# SFPGA_power.net
KiCad netlist of a schematic drawn in Altium Designer
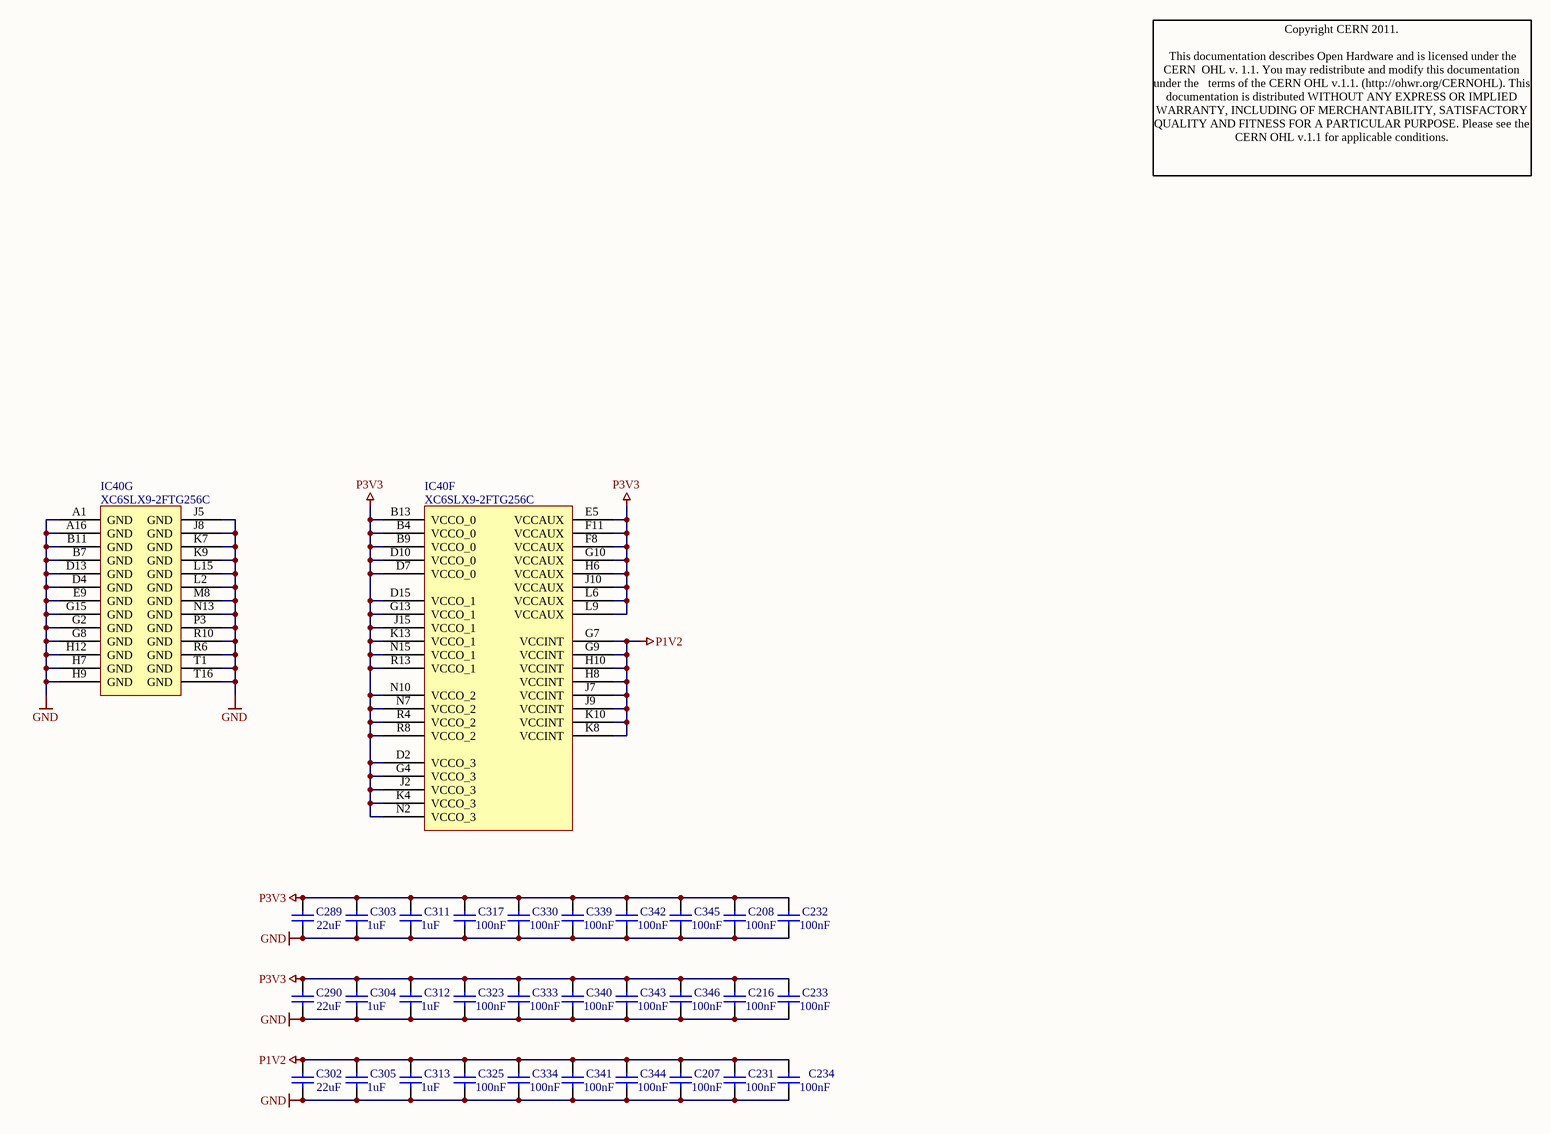
[diagram p0: SFPGA_power.SchDoc]

(export (version "E")
  (design (tool "Eeschema 10.0.6"))
  (components
    (comp (ref "C207")
      (value "100nF")
      (footprint "CAPC1005X55N")
      (description "Non-polarised capacitor")
      (fields
        (field (name "PART NUMBER") "CC0402_100NF_16V_10%_X7R")
        (field (name "VOLTAGE") "16V")
        (field (name "AUTHOR") "CERN DEM JLC")
      )
      (libsource (lib "Capacitors") (part "Capacitor - non polarized"))
    )
    (comp (ref "C208")
      (value "100nF")
      (footprint "CAPC1005X55N")
      (description "Non-polarised capacitor")
      (fields
        (field (name "PART NUMBER") "CC0402_100NF_16V_10%_X7R")
        (field (name "VOLTAGE") "16V")
        (field (name "AUTHOR") "CERN DEM JLC")
      )
      (libsource (lib "Capacitors") (part "Capacitor - non polarized"))
    )
    (comp (ref "C216")
      (value "100nF")
      (footprint "CAPC1005X55N")
      (description "Non-polarised capacitor")
      (fields
        (field (name "PART NUMBER") "CC0402_100NF_16V_10%_X7R")
        (field (name "VOLTAGE") "16V")
        (field (name "AUTHOR") "CERN DEM JLC")
      )
      (libsource (lib "Capacitors") (part "Capacitor - non polarized"))
    )
    (comp (ref "C231")
      (value "100nF")
      (footprint "CAPC1005X55N")
      (description "Non-polarised capacitor")
      (fields
        (field (name "PART NUMBER") "CC0402_100NF_16V_10%_X7R")
        (field (name "VOLTAGE") "16V")
        (field (name "AUTHOR") "CERN DEM JLC")
      )
      (libsource (lib "Capacitors") (part "Capacitor - non polarized"))
    )
    (comp (ref "C232")
      (value "100nF")
      (footprint "CAPC1005X55N")
      (description "Non-polarised capacitor")
      (fields
        (field (name "PART NUMBER") "CC0402_100NF_16V_10%_X7R")
        (field (name "VOLTAGE") "16V")
        (field (name "AUTHOR") "CERN DEM JLC")
      )
      (libsource (lib "Capacitors") (part "Capacitor - non polarized"))
    )
    (comp (ref "C233")
      (value "100nF")
      (footprint "CAPC1005X55N")
      (description "Non-polarised capacitor")
      (fields
        (field (name "PART NUMBER") "CC0402_100NF_16V_10%_X7R")
        (field (name "VOLTAGE") "16V")
        (field (name "AUTHOR") "CERN DEM JLC")
      )
      (libsource (lib "Capacitors") (part "Capacitor - non polarized"))
    )
    (comp (ref "C234")
      (value "100nF")
      (footprint "CAPC1005X55N")
      (description "Non-polarised capacitor")
      (fields
        (field (name "PART NUMBER") "CC0402_100NF_16V_10%_X7R")
        (field (name "VOLTAGE") "16V")
        (field (name "AUTHOR") "CERN DEM JLC")
      )
      (libsource (lib "Capacitors") (part "Capacitor - non polarized"))
    )
    (comp (ref "C289")
      (value "22uF")
      (footprint "CAPC3216X180N")
      (description "Non-polarised capacitor")
      (fields
        (field (name "PART NUMBER") "CC1206_22UF_10V_10%_X7R")
        (field (name "VOLTAGE") "10V")
        (field (name "AUTHOR") "CERN DEM JLC")
      )
      (libsource (lib "Capacitors") (part "Capacitor - non polarized"))
    )
    (comp (ref "C290")
      (value "22uF")
      (footprint "CAPC3216X180N")
      (description "Non-polarised capacitor")
      (fields
        (field (name "PART NUMBER") "CC1206_22UF_10V_10%_X7R")
        (field (name "VOLTAGE") "10V")
        (field (name "AUTHOR") "CERN DEM JLC")
      )
      (libsource (lib "Capacitors") (part "Capacitor - non polarized"))
    )
    (comp (ref "C302")
      (value "22uF")
      (footprint "CAPC3216X180N")
      (description "Non-polarised capacitor")
      (fields
        (field (name "PART NUMBER") "CC1206_22UF_10V_10%_X7R")
        (field (name "VOLTAGE") "10V")
        (field (name "AUTHOR") "CERN DEM JLC")
      )
      (libsource (lib "Capacitors") (part "Capacitor - non polarized"))
    )
    (comp (ref "C303")
      (value "1uF")
      (footprint "CAPC1608X87N")
      (description "Non-polarised capacitor")
      (fields
        (field (name "PART NUMBER") "CC0603_1UF_16V_10%_X7R")
        (field (name "VOLTAGE") "16V")
        (field (name "AUTHOR") "CERN DEM JLC")
      )
      (libsource (lib "Capacitors") (part "Capacitor - non polarized"))
    )
    (comp (ref "C304")
      (value "1uF")
      (footprint "CAPC1608X87N")
      (description "Non-polarised capacitor")
      (fields
        (field (name "PART NUMBER") "CC0603_1UF_16V_10%_X7R")
        (field (name "VOLTAGE") "16V")
        (field (name "AUTHOR") "CERN DEM JLC")
      )
      (libsource (lib "Capacitors") (part "Capacitor - non polarized"))
    )
    (comp (ref "C305")
      (value "1uF")
      (footprint "CAPC1608X87N")
      (description "Non-polarised capacitor")
      (fields
        (field (name "PART NUMBER") "CC0603_1UF_16V_10%_X7R")
        (field (name "VOLTAGE") "16V")
        (field (name "AUTHOR") "CERN DEM JLC")
      )
      (libsource (lib "Capacitors") (part "Capacitor - non polarized"))
    )
    (comp (ref "C311")
      (value "1uF")
      (footprint "CAPC1608X87N")
      (description "Non-polarised capacitor")
      (fields
        (field (name "PART NUMBER") "CC0603_1UF_16V_10%_X7R")
        (field (name "VOLTAGE") "16V")
        (field (name "AUTHOR") "CERN DEM JLC")
      )
      (libsource (lib "Capacitors") (part "Capacitor - non polarized"))
    )
    (comp (ref "C312")
      (value "1uF")
      (footprint "CAPC1608X87N")
      (description "Non-polarised capacitor")
      (fields
        (field (name "PART NUMBER") "CC0603_1UF_16V_10%_X7R")
        (field (name "VOLTAGE") "16V")
        (field (name "AUTHOR") "CERN DEM JLC")
      )
      (libsource (lib "Capacitors") (part "Capacitor - non polarized"))
    )
    (comp (ref "C313")
      (value "1uF")
      (footprint "CAPC1608X87N")
      (description "Non-polarised capacitor")
      (fields
        (field (name "PART NUMBER") "CC0603_1UF_16V_10%_X7R")
        (field (name "VOLTAGE") "16V")
        (field (name "AUTHOR") "CERN DEM JLC")
      )
      (libsource (lib "Capacitors") (part "Capacitor - non polarized"))
    )
    (comp (ref "C317")
      (value "100nF")
      (footprint "CAPC1005X55N")
      (description "Non-polarised capacitor")
      (fields
        (field (name "PART NUMBER") "CC0402_100NF_16V_10%_X7R")
        (field (name "VOLTAGE") "16V")
        (field (name "AUTHOR") "CERN DEM JLC")
      )
      (libsource (lib "Capacitors") (part "Capacitor - non polarized"))
    )
    (comp (ref "C323")
      (value "100nF")
      (footprint "CAPC1005X55N")
      (description "Non-polarised capacitor")
      (fields
        (field (name "PART NUMBER") "CC0402_100NF_16V_10%_X7R")
        (field (name "VOLTAGE") "16V")
        (field (name "AUTHOR") "CERN DEM JLC")
      )
      (libsource (lib "Capacitors") (part "Capacitor - non polarized"))
    )
    (comp (ref "C325")
      (value "100nF")
      (footprint "CAPC1005X55N")
      (description "Non-polarised capacitor")
      (fields
        (field (name "PART NUMBER") "CC0402_100NF_16V_10%_X7R")
        (field (name "VOLTAGE") "16V")
        (field (name "AUTHOR") "CERN DEM JLC")
      )
      (libsource (lib "Capacitors") (part "Capacitor - non polarized"))
    )
    (comp (ref "C330")
      (value "100nF")
      (footprint "CAPC1005X55N")
      (description "Non-polarised capacitor")
      (fields
        (field (name "PART NUMBER") "CC0402_100NF_16V_10%_X7R")
        (field (name "VOLTAGE") "16V")
        (field (name "AUTHOR") "CERN DEM JLC")
      )
      (libsource (lib "Capacitors") (part "Capacitor - non polarized"))
    )
    (comp (ref "C333")
      (value "100nF")
      (footprint "CAPC1005X55N")
      (description "Non-polarised capacitor")
      (fields
        (field (name "PART NUMBER") "CC0402_100NF_16V_10%_X7R")
        (field (name "VOLTAGE") "16V")
        (field (name "AUTHOR") "CERN DEM JLC")
      )
      (libsource (lib "Capacitors") (part "Capacitor - non polarized"))
    )
    (comp (ref "C334")
      (value "100nF")
      (footprint "CAPC1005X55N")
      (description "Non-polarised capacitor")
      (fields
        (field (name "PART NUMBER") "CC0402_100NF_16V_10%_X7R")
        (field (name "VOLTAGE") "16V")
        (field (name "AUTHOR") "CERN DEM JLC")
      )
      (libsource (lib "Capacitors") (part "Capacitor - non polarized"))
    )
    (comp (ref "C339")
      (value "100nF")
      (footprint "CAPC1005X55N")
      (description "Non-polarised capacitor")
      (fields
        (field (name "PART NUMBER") "CC0402_100NF_16V_10%_X7R")
        (field (name "VOLTAGE") "16V")
        (field (name "AUTHOR") "CERN DEM JLC")
      )
      (libsource (lib "Capacitors") (part "Capacitor - non polarized"))
    )
    (comp (ref "C340")
      (value "100nF")
      (footprint "CAPC1005X55N")
      (description "Non-polarised capacitor")
      (fields
        (field (name "PART NUMBER") "CC0402_100NF_16V_10%_X7R")
        (field (name "VOLTAGE") "16V")
        (field (name "AUTHOR") "CERN DEM JLC")
      )
      (libsource (lib "Capacitors") (part "Capacitor - non polarized"))
    )
    (comp (ref "C341")
      (value "100nF")
      (footprint "CAPC1005X55N")
      (description "Non-polarised capacitor")
      (fields
        (field (name "PART NUMBER") "CC0402_100NF_16V_10%_X7R")
        (field (name "VOLTAGE") "16V")
        (field (name "AUTHOR") "CERN DEM JLC")
      )
      (libsource (lib "Capacitors") (part "Capacitor - non polarized"))
    )
    (comp (ref "C342")
      (value "100nF")
      (footprint "CAPC1005X55N")
      (description "Non-polarised capacitor")
      (fields
        (field (name "PART NUMBER") "CC0402_100NF_16V_10%_X7R")
        (field (name "VOLTAGE") "16V")
        (field (name "AUTHOR") "CERN DEM JLC")
      )
      (libsource (lib "Capacitors") (part "Capacitor - non polarized"))
    )
    (comp (ref "C343")
      (value "100nF")
      (footprint "CAPC1005X55N")
      (description "Non-polarised capacitor")
      (fields
        (field (name "PART NUMBER") "CC0402_100NF_16V_10%_X7R")
        (field (name "VOLTAGE") "16V")
        (field (name "AUTHOR") "CERN DEM JLC")
      )
      (libsource (lib "Capacitors") (part "Capacitor - non polarized"))
    )
    (comp (ref "C344")
      (value "100nF")
      (footprint "CAPC1005X55N")
      (description "Non-polarised capacitor")
      (fields
        (field (name "PART NUMBER") "CC0402_100NF_16V_10%_X7R")
        (field (name "VOLTAGE") "16V")
        (field (name "AUTHOR") "CERN DEM JLC")
      )
      (libsource (lib "Capacitors") (part "Capacitor - non polarized"))
    )
    (comp (ref "C345")
      (value "100nF")
      (footprint "CAPC1005X55N")
      (description "Non-polarised capacitor")
      (fields
        (field (name "PART NUMBER") "CC0402_100NF_16V_10%_X7R")
        (field (name "VOLTAGE") "16V")
        (field (name "AUTHOR") "CERN DEM JLC")
      )
      (libsource (lib "Capacitors") (part "Capacitor - non polarized"))
    )
    (comp (ref "C346")
      (value "100nF")
      (footprint "CAPC1005X55N")
      (description "Non-polarised capacitor")
      (fields
        (field (name "PART NUMBER") "CC0402_100NF_16V_10%_X7R")
        (field (name "VOLTAGE") "16V")
        (field (name "AUTHOR") "CERN DEM JLC")
      )
      (libsource (lib "Capacitors") (part "Capacitor - non polarized"))
    )
    (comp (ref "IC40")
      (value "XC6SLX9-2FTG256C")
      (footprint "BGA256C100P16X16_1700X1700X155")
      (fields (field (name "MANUFACTURER") "XILINX") (field (name "AUTHOR") "CERN DEM JLC"))
      (libsource (lib "ICs And Semiconductors") (part "XC6SLX9-2FTG256C"))
    )
  )
  (nets
    (net (code "1") (name "GND") (class "Default")
      (node (ref "C207") (pin "1") (pinfunction "1_1") (pintype "passive"))
      (node (ref "C208") (pin "1") (pinfunction "1_1") (pintype "passive"))
      (node (ref "C216") (pin "1") (pinfunction "1_1") (pintype "passive"))
      (node (ref "C231") (pin "1") (pinfunction "1_1") (pintype "passive"))
      (node (ref "C232") (pin "1") (pinfunction "1_1") (pintype "passive"))
      (node (ref "C233") (pin "1") (pinfunction "1_1") (pintype "passive"))
      (node (ref "C234") (pin "1") (pinfunction "1_1") (pintype "passive"))
      (node (ref "C289") (pin "1") (pinfunction "1_1") (pintype "passive"))
      (node (ref "C290") (pin "1") (pinfunction "1_1") (pintype "passive"))
      (node (ref "C302") (pin "1") (pinfunction "1_1") (pintype "passive"))
      (node (ref "C303") (pin "1") (pinfunction "1_1") (pintype "passive"))
      (node (ref "C304") (pin "1") (pinfunction "1_1") (pintype "passive"))
      (node (ref "C305") (pin "1") (pinfunction "1_1") (pintype "passive"))
      (node (ref "C311") (pin "1") (pinfunction "1_1") (pintype "passive"))
      (node (ref "C312") (pin "1") (pinfunction "1_1") (pintype "passive"))
      (node (ref "C313") (pin "1") (pinfunction "1_1") (pintype "passive"))
      (node (ref "C317") (pin "1") (pinfunction "1_1") (pintype "passive"))
      (node (ref "C323") (pin "1") (pinfunction "1_1") (pintype "passive"))
      (node (ref "C325") (pin "1") (pinfunction "1_1") (pintype "passive"))
      (node (ref "C330") (pin "1") (pinfunction "1_1") (pintype "passive"))
      (node (ref "C333") (pin "1") (pinfunction "1_1") (pintype "passive"))
      (node (ref "C334") (pin "1") (pinfunction "1_1") (pintype "passive"))
      (node (ref "C339") (pin "1") (pinfunction "1_1") (pintype "passive"))
      (node (ref "C340") (pin "1") (pinfunction "1_1") (pintype "passive"))
      (node (ref "C341") (pin "1") (pinfunction "1_1") (pintype "passive"))
      (node (ref "C342") (pin "1") (pinfunction "1_1") (pintype "passive"))
      (node (ref "C343") (pin "1") (pinfunction "1_1") (pintype "passive"))
      (node (ref "C344") (pin "1") (pinfunction "1_1") (pintype "passive"))
      (node (ref "C345") (pin "1") (pinfunction "1_1") (pintype "passive"))
      (node (ref "C346") (pin "1") (pinfunction "1_1") (pintype "passive"))
      (node (ref "IC40") (pin "A1") (pinfunction "GND_A1") (pintype "power_in"))
      (node (ref "IC40") (pin "A16") (pinfunction "GND_A16") (pintype "power_in"))
      (node (ref "IC40") (pin "B11") (pinfunction "GND_B11") (pintype "power_in"))
      (node (ref "IC40") (pin "B7") (pinfunction "GND_B7") (pintype "power_in"))
      (node (ref "IC40") (pin "D13") (pinfunction "GND_D13") (pintype "power_in"))
      (node (ref "IC40") (pin "D4") (pinfunction "GND_D4") (pintype "power_in"))
      (node (ref "IC40") (pin "E9") (pinfunction "GND_E9") (pintype "power_in"))
      (node (ref "IC40") (pin "G15") (pinfunction "GND_G15") (pintype "power_in"))
      (node (ref "IC40") (pin "G2") (pinfunction "GND_G2") (pintype "power_in"))
      (node (ref "IC40") (pin "G8") (pinfunction "GND_G8") (pintype "power_in"))
      (node (ref "IC40") (pin "H12") (pinfunction "GND_H12") (pintype "power_in"))
      (node (ref "IC40") (pin "H7") (pinfunction "GND_H7") (pintype "power_in"))
      (node (ref "IC40") (pin "H9") (pinfunction "GND_H9") (pintype "power_in"))
      (node (ref "IC40") (pin "J5") (pinfunction "GND_J5") (pintype "power_in"))
      (node (ref "IC40") (pin "J8") (pinfunction "GND_J8") (pintype "power_in"))
      (node (ref "IC40") (pin "K7") (pinfunction "GND_K7") (pintype "power_in"))
      (node (ref "IC40") (pin "K9") (pinfunction "GND_K9") (pintype "power_in"))
      (node (ref "IC40") (pin "L15") (pinfunction "GND_L15") (pintype "power_in"))
      (node (ref "IC40") (pin "L2") (pinfunction "GND_L2") (pintype "power_in"))
      (node (ref "IC40") (pin "M8") (pinfunction "GND_M8") (pintype "power_in"))
      (node (ref "IC40") (pin "N13") (pinfunction "GND_N13") (pintype "power_in"))
      (node (ref "IC40") (pin "P3") (pinfunction "GND_P3") (pintype "power_in"))
      (node (ref "IC40") (pin "R10") (pinfunction "GND_R10") (pintype "power_in"))
      (node (ref "IC40") (pin "R6") (pinfunction "GND_R6") (pintype "power_in"))
      (node (ref "IC40") (pin "T1") (pinfunction "GND_T1") (pintype "power_in"))
      (node (ref "IC40") (pin "T16") (pinfunction "GND_T16") (pintype "power_in"))
    )
    (net (code "2") (name "P1V2") (class "Default")
      (node (ref "C207") (pin "2") (pinfunction "2_2") (pintype "passive"))
      (node (ref "C231") (pin "2") (pinfunction "2_2") (pintype "passive"))
      (node (ref "C234") (pin "2") (pinfunction "2_2") (pintype "passive"))
      (node (ref "C302") (pin "2") (pinfunction "2_2") (pintype "passive"))
      (node (ref "C305") (pin "2") (pinfunction "2_2") (pintype "passive"))
      (node (ref "C313") (pin "2") (pinfunction "2_2") (pintype "passive"))
      (node (ref "C325") (pin "2") (pinfunction "2_2") (pintype "passive"))
      (node (ref "C334") (pin "2") (pinfunction "2_2") (pintype "passive"))
      (node (ref "C341") (pin "2") (pinfunction "2_2") (pintype "passive"))
      (node (ref "C344") (pin "2") (pinfunction "2_2") (pintype "passive"))
      (node (ref "IC40") (pin "G7") (pinfunction "VCCINT_G7") (pintype "power_in"))
      (node (ref "IC40") (pin "G9") (pinfunction "VCCINT_G9") (pintype "power_in"))
      (node (ref "IC40") (pin "H10") (pinfunction "VCCINT_H10") (pintype "power_in"))
      (node (ref "IC40") (pin "H8") (pinfunction "VCCINT_H8") (pintype "power_in"))
      (node (ref "IC40") (pin "J7") (pinfunction "VCCINT_J7") (pintype "power_in"))
      (node (ref "IC40") (pin "J9") (pinfunction "VCCINT_J9") (pintype "power_in"))
      (node (ref "IC40") (pin "K10") (pinfunction "VCCINT_K10") (pintype "power_in"))
      (node (ref "IC40") (pin "K8") (pinfunction "VCCINT_K8") (pintype "power_in"))
    )
    (net (code "3") (name "P3V3") (class "Default")
      (node (ref "C208") (pin "2") (pinfunction "2_2") (pintype "passive"))
      (node (ref "C216") (pin "2") (pinfunction "2_2") (pintype "passive"))
      (node (ref "C232") (pin "2") (pinfunction "2_2") (pintype "passive"))
      (node (ref "C233") (pin "2") (pinfunction "2_2") (pintype "passive"))
      (node (ref "C289") (pin "2") (pinfunction "2_2") (pintype "passive"))
      (node (ref "C290") (pin "2") (pinfunction "2_2") (pintype "passive"))
      (node (ref "C303") (pin "2") (pinfunction "2_2") (pintype "passive"))
      (node (ref "C304") (pin "2") (pinfunction "2_2") (pintype "passive"))
      (node (ref "C311") (pin "2") (pinfunction "2_2") (pintype "passive"))
      (node (ref "C312") (pin "2") (pinfunction "2_2") (pintype "passive"))
      (node (ref "C317") (pin "2") (pinfunction "2_2") (pintype "passive"))
      (node (ref "C323") (pin "2") (pinfunction "2_2") (pintype "passive"))
      (node (ref "C330") (pin "2") (pinfunction "2_2") (pintype "passive"))
      (node (ref "C333") (pin "2") (pinfunction "2_2") (pintype "passive"))
      (node (ref "C339") (pin "2") (pinfunction "2_2") (pintype "passive"))
      (node (ref "C340") (pin "2") (pinfunction "2_2") (pintype "passive"))
      (node (ref "C342") (pin "2") (pinfunction "2_2") (pintype "passive"))
      (node (ref "C343") (pin "2") (pinfunction "2_2") (pintype "passive"))
      (node (ref "C345") (pin "2") (pinfunction "2_2") (pintype "passive"))
      (node (ref "C346") (pin "2") (pinfunction "2_2") (pintype "passive"))
      (node (ref "IC40") (pin "B13") (pinfunction "VCCO_0_B13") (pintype "power_in"))
      (node (ref "IC40") (pin "B4") (pinfunction "VCCO_0_B4") (pintype "power_in"))
      (node (ref "IC40") (pin "B9") (pinfunction "VCCO_0_B9") (pintype "power_in"))
      (node (ref "IC40") (pin "D10") (pinfunction "VCCO_0_D10") (pintype "power_in"))
      (node (ref "IC40") (pin "D15") (pinfunction "VCCO_1_D15") (pintype "power_in"))
      (node (ref "IC40") (pin "D2") (pinfunction "VCCO_3_D2") (pintype "power_in"))
      (node (ref "IC40") (pin "D7") (pinfunction "VCCO_0_D7") (pintype "power_in"))
      (node (ref "IC40") (pin "E5") (pinfunction "VCCAUX_E5") (pintype "power_in"))
      (node (ref "IC40") (pin "F11") (pinfunction "VCCAUX_F11") (pintype "power_in"))
      (node (ref "IC40") (pin "F8") (pinfunction "VCCAUX_F8") (pintype "power_in"))
      (node (ref "IC40") (pin "G10") (pinfunction "VCCAUX_G10") (pintype "power_in"))
      (node (ref "IC40") (pin "G13") (pinfunction "VCCO_1_G13") (pintype "power_in"))
      (node (ref "IC40") (pin "G4") (pinfunction "VCCO_3_G4") (pintype "power_in"))
      (node (ref "IC40") (pin "H6") (pinfunction "VCCAUX_H6") (pintype "power_in"))
      (node (ref "IC40") (pin "J10") (pinfunction "VCCAUX_J10") (pintype "power_in"))
      (node (ref "IC40") (pin "J15") (pinfunction "VCCO_1_J15") (pintype "power_in"))
      (node (ref "IC40") (pin "J2") (pinfunction "VCCO_3_J2") (pintype "power_in"))
      (node (ref "IC40") (pin "K13") (pinfunction "VCCO_1_K13") (pintype "power_in"))
      (node (ref "IC40") (pin "K4") (pinfunction "VCCO_3_K4") (pintype "power_in"))
      (node (ref "IC40") (pin "L6") (pinfunction "VCCAUX_L6") (pintype "power_in"))
      (node (ref "IC40") (pin "L9") (pinfunction "VCCAUX_L9") (pintype "power_in"))
      (node (ref "IC40") (pin "N10") (pinfunction "VCCO_2_N10") (pintype "power_in"))
      (node (ref "IC40") (pin "N15") (pinfunction "VCCO_1_N15") (pintype "power_in"))
      (node (ref "IC40") (pin "N2") (pinfunction "VCCO_3_N2") (pintype "power_in"))
      (node (ref "IC40") (pin "N7") (pinfunction "VCCO_2_N7") (pintype "power_in"))
      (node (ref "IC40") (pin "R13") (pinfunction "VCCO_1_R13") (pintype "power_in"))
      (node (ref "IC40") (pin "R4") (pinfunction "VCCO_2_R4") (pintype "power_in"))
      (node (ref "IC40") (pin "R8") (pinfunction "VCCO_2_R8") (pintype "power_in"))
    )
  )
)
